# 16ServosController.net
KiCad netlist of a schematic drawn in EAGLE
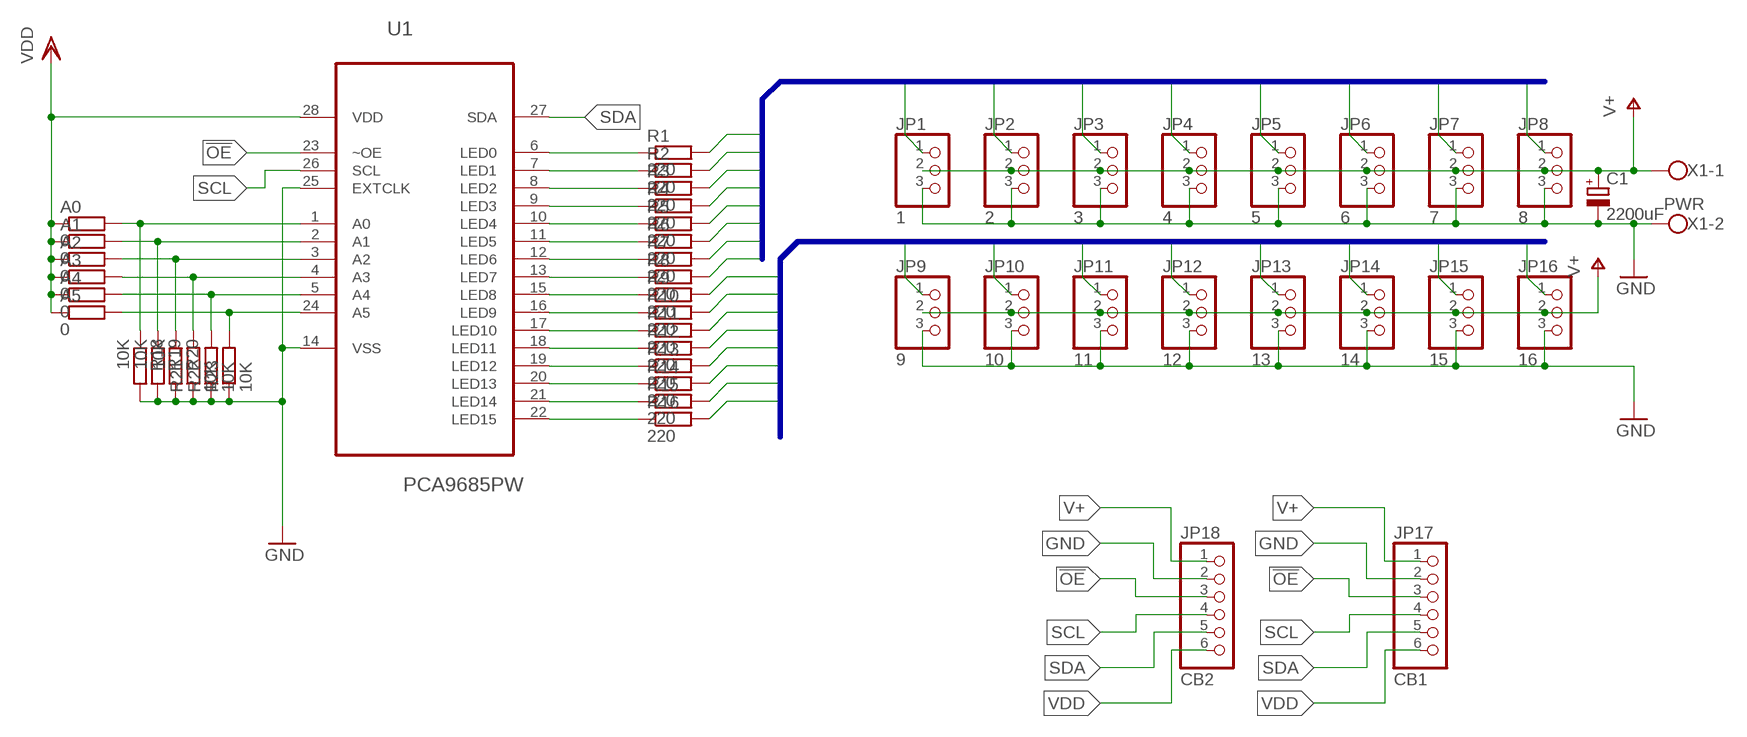
[diagram p0: schematic, sheet 1]

(export (version "E")
  (design (tool "Eeschema 10.0.6"))
  (components
    (comp (ref "A0")
      (value "0")
      (footprint "eagle-import:R0805")
      (libsource (lib "eagle-import") (part "R-EU_R0805"))
    )
    (comp (ref "A1")
      (value "0")
      (footprint "eagle-import:R0805")
      (libsource (lib "eagle-import") (part "R-EU_R0805"))
    )
    (comp (ref "A2")
      (value "0")
      (footprint "eagle-import:R0805")
      (libsource (lib "eagle-import") (part "R-EU_R0805"))
    )
    (comp (ref "A3")
      (value "0")
      (footprint "eagle-import:R0805")
      (libsource (lib "eagle-import") (part "R-EU_R0805"))
    )
    (comp (ref "A4")
      (value "0")
      (footprint "eagle-import:R0805")
      (libsource (lib "eagle-import") (part "R-EU_R0805"))
    )
    (comp (ref "A5")
      (value "0")
      (footprint "eagle-import:R0805")
      (libsource (lib "eagle-import") (part "R-EU_R0805"))
    )
    (comp (ref "C1")
      (value "2200uF")
      (footprint "eagle-import:E5-6")
      (libsource (lib "eagle-import") (part "CPOL-EUE5-6"))
    )
    (comp (ref "JP1")
      (value "1")
      (footprint "eagle-import:1X03")
      (libsource (lib "eagle-import") (part "PINHD-1X3"))
    )
    (comp (ref "JP2")
      (value "2")
      (footprint "eagle-import:1X03")
      (libsource (lib "eagle-import") (part "PINHD-1X3"))
    )
    (comp (ref "JP3")
      (value "3")
      (footprint "eagle-import:1X03")
      (libsource (lib "eagle-import") (part "PINHD-1X3"))
    )
    (comp (ref "JP4")
      (value "4")
      (footprint "eagle-import:1X03")
      (libsource (lib "eagle-import") (part "PINHD-1X3"))
    )
    (comp (ref "JP5")
      (value "5")
      (footprint "eagle-import:1X03")
      (libsource (lib "eagle-import") (part "PINHD-1X3"))
    )
    (comp (ref "JP6")
      (value "6")
      (footprint "eagle-import:1X03")
      (libsource (lib "eagle-import") (part "PINHD-1X3"))
    )
    (comp (ref "JP7")
      (value "7")
      (footprint "eagle-import:1X03")
      (libsource (lib "eagle-import") (part "PINHD-1X3"))
    )
    (comp (ref "JP8")
      (value "8")
      (footprint "eagle-import:1X03")
      (libsource (lib "eagle-import") (part "PINHD-1X3"))
    )
    (comp (ref "JP9")
      (value "9")
      (footprint "eagle-import:1X03")
      (libsource (lib "eagle-import") (part "PINHD-1X3"))
    )
    (comp (ref "JP10")
      (value "10")
      (footprint "eagle-import:1X03")
      (libsource (lib "eagle-import") (part "PINHD-1X3"))
    )
    (comp (ref "JP11")
      (value "11")
      (footprint "eagle-import:1X03")
      (libsource (lib "eagle-import") (part "PINHD-1X3"))
    )
    (comp (ref "JP12")
      (value "12")
      (footprint "eagle-import:1X03")
      (libsource (lib "eagle-import") (part "PINHD-1X3"))
    )
    (comp (ref "JP13")
      (value "13")
      (footprint "eagle-import:1X03")
      (libsource (lib "eagle-import") (part "PINHD-1X3"))
    )
    (comp (ref "JP14")
      (value "14")
      (footprint "eagle-import:1X03")
      (libsource (lib "eagle-import") (part "PINHD-1X3"))
    )
    (comp (ref "JP15")
      (value "15")
      (footprint "eagle-import:1X03")
      (libsource (lib "eagle-import") (part "PINHD-1X3"))
    )
    (comp (ref "JP16")
      (value "16")
      (footprint "eagle-import:1X03")
      (libsource (lib "eagle-import") (part "PINHD-1X3"))
    )
    (comp (ref "JP17")
      (value "CB1")
      (footprint "eagle-import:1X06")
      (libsource (lib "eagle-import") (part "PINHD-1X6"))
    )
    (comp (ref "JP18")
      (value "CB2")
      (footprint "eagle-import:1X06")
      (libsource (lib "eagle-import") (part "PINHD-1X6"))
    )
    (comp (ref "R1")
      (value "220")
      (footprint "eagle-import:R0805")
      (libsource (lib "eagle-import") (part "R-EU_R0805"))
    )
    (comp (ref "R2")
      (value "220")
      (footprint "eagle-import:R0805")
      (libsource (lib "eagle-import") (part "R-EU_R0805"))
    )
    (comp (ref "R3")
      (value "220")
      (footprint "eagle-import:R0805")
      (libsource (lib "eagle-import") (part "R-EU_R0805"))
    )
    (comp (ref "R4")
      (value "220")
      (footprint "eagle-import:R0805")
      (libsource (lib "eagle-import") (part "R-EU_R0805"))
    )
    (comp (ref "R5")
      (value "220")
      (footprint "eagle-import:R0805")
      (libsource (lib "eagle-import") (part "R-EU_R0805"))
    )
    (comp (ref "R6")
      (value "220")
      (footprint "eagle-import:R0805")
      (libsource (lib "eagle-import") (part "R-EU_R0805"))
    )
    (comp (ref "R7")
      (value "220")
      (footprint "eagle-import:R0805")
      (libsource (lib "eagle-import") (part "R-EU_R0805"))
    )
    (comp (ref "R8")
      (value "220")
      (footprint "eagle-import:R0805")
      (libsource (lib "eagle-import") (part "R-EU_R0805"))
    )
    (comp (ref "R9")
      (value "220")
      (footprint "eagle-import:R0805")
      (libsource (lib "eagle-import") (part "R-EU_R0805"))
    )
    (comp (ref "R10")
      (value "220")
      (footprint "eagle-import:R0805")
      (libsource (lib "eagle-import") (part "R-EU_R0805"))
    )
    (comp (ref "R11")
      (value "220")
      (footprint "eagle-import:R0805")
      (libsource (lib "eagle-import") (part "R-EU_R0805"))
    )
    (comp (ref "R12")
      (value "220")
      (footprint "eagle-import:R0805")
      (libsource (lib "eagle-import") (part "R-EU_R0805"))
    )
    (comp (ref "R13")
      (value "220")
      (footprint "eagle-import:R0805")
      (libsource (lib "eagle-import") (part "R-EU_R0805"))
    )
    (comp (ref "R14")
      (value "220")
      (footprint "eagle-import:R0805")
      (libsource (lib "eagle-import") (part "R-EU_R0805"))
    )
    (comp (ref "R15")
      (value "220")
      (footprint "eagle-import:R0805")
      (libsource (lib "eagle-import") (part "R-EU_R0805"))
    )
    (comp (ref "R16")
      (value "220")
      (footprint "eagle-import:R0805")
      (libsource (lib "eagle-import") (part "R-EU_R0805"))
    )
    (comp (ref "R18")
      (value "10K")
      (footprint "eagle-import:R0805")
      (libsource (lib "eagle-import") (part "R-EU_R0805"))
    )
    (comp (ref "R19")
      (value "10K")
      (footprint "eagle-import:R0805")
      (libsource (lib "eagle-import") (part "R-EU_R0805"))
    )
    (comp (ref "R20")
      (value "10K")
      (footprint "eagle-import:R0805")
      (libsource (lib "eagle-import") (part "R-EU_R0805"))
    )
    (comp (ref "R21")
      (value "10K")
      (footprint "eagle-import:R0805")
      (libsource (lib "eagle-import") (part "R-EU_R0805"))
    )
    (comp (ref "R22")
      (value "10K")
      (footprint "eagle-import:R0805")
      (libsource (lib "eagle-import") (part "R-EU_R0805"))
    )
    (comp (ref "R23")
      (value "10K")
      (footprint "eagle-import:R0805")
      (libsource (lib "eagle-import") (part "R-EU_R0805"))
    )
    (comp (ref "U1")
      (value "PCA9685PW")
      (footprint "eagle-import:SOP65P640X110-28N")
      (libsource (lib "eagle-import") (part "PCA9685PW"))
    )
    (comp (ref "X1")
      (value "PWR")
      (footprint "eagle-import:W237-102")
      (fields (field (name "MPN") "237-102"))
      (libsource (lib "eagle-import") (part "W237-102"))
    )
  )
  (nets
    (net (code "1") (name "/PWM1") (class "Default")
      (node (ref "JP1") (pin "1") (pinfunction "1_1") (pintype "passive"))
      (node (ref "R1") (pin "2") (pinfunction "2_2") (pintype "passive"))
    )
    (net (code "2") (name "/PWM2") (class "Default")
      (node (ref "JP2") (pin "1") (pinfunction "1_1") (pintype "passive"))
      (node (ref "R2") (pin "2") (pinfunction "2_2") (pintype "passive"))
    )
    (net (code "3") (name "/PWM3") (class "Default")
      (node (ref "JP3") (pin "1") (pinfunction "1_1") (pintype "passive"))
      (node (ref "R3") (pin "2") (pinfunction "2_2") (pintype "passive"))
    )
    (net (code "4") (name "/PWM4") (class "Default")
      (node (ref "JP4") (pin "1") (pinfunction "1_1") (pintype "passive"))
      (node (ref "R4") (pin "2") (pinfunction "2_2") (pintype "passive"))
    )
    (net (code "5") (name "/PWM5") (class "Default")
      (node (ref "JP5") (pin "1") (pinfunction "1_1") (pintype "passive"))
      (node (ref "R5") (pin "2") (pinfunction "2_2") (pintype "passive"))
    )
    (net (code "6") (name "/PWM6") (class "Default")
      (node (ref "JP6") (pin "1") (pinfunction "1_1") (pintype "passive"))
      (node (ref "R6") (pin "2") (pinfunction "2_2") (pintype "passive"))
    )
    (net (code "7") (name "/PWM7") (class "Default")
      (node (ref "JP7") (pin "1") (pinfunction "1_1") (pintype "passive"))
      (node (ref "R7") (pin "2") (pinfunction "2_2") (pintype "passive"))
    )
    (net (code "8") (name "/PWM8") (class "Default")
      (node (ref "JP8") (pin "1") (pinfunction "1_1") (pintype "passive"))
      (node (ref "R8") (pin "2") (pinfunction "2_2") (pintype "passive"))
    )
    (net (code "9") (name "/PWM9") (class "Default")
      (node (ref "JP9") (pin "1") (pinfunction "1_1") (pintype "passive"))
      (node (ref "R9") (pin "2") (pinfunction "2_2") (pintype "passive"))
    )
    (net (code "10") (name "/PWM10") (class "Default")
      (node (ref "JP10") (pin "1") (pinfunction "1_1") (pintype "passive"))
      (node (ref "R10") (pin "2") (pinfunction "2_2") (pintype "passive"))
    )
    (net (code "11") (name "/PWM11") (class "Default")
      (node (ref "JP11") (pin "1") (pinfunction "1_1") (pintype "passive"))
      (node (ref "R11") (pin "2") (pinfunction "2_2") (pintype "passive"))
    )
    (net (code "12") (name "/PWM12") (class "Default")
      (node (ref "JP12") (pin "1") (pinfunction "1_1") (pintype "passive"))
      (node (ref "R12") (pin "2") (pinfunction "2_2") (pintype "passive"))
    )
    (net (code "13") (name "/PWM13") (class "Default")
      (node (ref "JP13") (pin "1") (pinfunction "1_1") (pintype "passive"))
      (node (ref "R13") (pin "2") (pinfunction "2_2") (pintype "passive"))
    )
    (net (code "14") (name "/PWM14") (class "Default")
      (node (ref "JP14") (pin "1") (pinfunction "1_1") (pintype "passive"))
      (node (ref "R14") (pin "2") (pinfunction "2_2") (pintype "passive"))
    )
    (net (code "15") (name "/PWM15") (class "Default")
      (node (ref "JP15") (pin "1") (pinfunction "1_1") (pintype "passive"))
      (node (ref "R15") (pin "2") (pinfunction "2_2") (pintype "passive"))
    )
    (net (code "16") (name "/PWM16") (class "Default")
      (node (ref "JP16") (pin "1") (pinfunction "1_1") (pintype "passive"))
      (node (ref "R16") (pin "2") (pinfunction "2_2") (pintype "passive"))
    )
    (net (code "17") (name "/~{OE}") (class "Default")
      (node (ref "JP17") (pin "3") (pinfunction "3_3") (pintype "passive"))
      (node (ref "JP18") (pin "3") (pinfunction "3_3") (pintype "passive"))
      (node (ref "U1") (pin "23") (pinfunction "~{OE}_23") (pintype "input"))
    )
    (net (code "18") (name "GND") (class "Default")
      (node (ref "C1") (pin "-") (pinfunction "-_-") (pintype "passive"))
      (node (ref "JP1") (pin "3") (pinfunction "3_3") (pintype "passive"))
      (node (ref "JP10") (pin "3") (pinfunction "3_3") (pintype "passive"))
      (node (ref "JP11") (pin "3") (pinfunction "3_3") (pintype "passive"))
      (node (ref "JP12") (pin "3") (pinfunction "3_3") (pintype "passive"))
      (node (ref "JP13") (pin "3") (pinfunction "3_3") (pintype "passive"))
      (node (ref "JP14") (pin "3") (pinfunction "3_3") (pintype "passive"))
      (node (ref "JP15") (pin "3") (pinfunction "3_3") (pintype "passive"))
      (node (ref "JP16") (pin "3") (pinfunction "3_3") (pintype "passive"))
      (node (ref "JP17") (pin "2") (pinfunction "2_2") (pintype "passive"))
      (node (ref "JP18") (pin "2") (pinfunction "2_2") (pintype "passive"))
      (node (ref "JP2") (pin "3") (pinfunction "3_3") (pintype "passive"))
      (node (ref "JP3") (pin "3") (pinfunction "3_3") (pintype "passive"))
      (node (ref "JP4") (pin "3") (pinfunction "3_3") (pintype "passive"))
      (node (ref "JP5") (pin "3") (pinfunction "3_3") (pintype "passive"))
      (node (ref "JP6") (pin "3") (pinfunction "3_3") (pintype "passive"))
      (node (ref "JP7") (pin "3") (pinfunction "3_3") (pintype "passive"))
      (node (ref "JP8") (pin "3") (pinfunction "3_3") (pintype "passive"))
      (node (ref "JP9") (pin "3") (pinfunction "3_3") (pintype "passive"))
      (node (ref "R18") (pin "2") (pinfunction "2_2") (pintype "passive"))
      (node (ref "R19") (pin "2") (pinfunction "2_2") (pintype "passive"))
      (node (ref "R20") (pin "2") (pinfunction "2_2") (pintype "passive"))
      (node (ref "R21") (pin "1") (pinfunction "1_1") (pintype "passive"))
      (node (ref "R22") (pin "1") (pinfunction "1_1") (pintype "passive"))
      (node (ref "R23") (pin "1") (pinfunction "1_1") (pintype "passive"))
      (node (ref "U1") (pin "14") (pinfunction "VSS_14") (pintype "passive"))
      (node (ref "U1") (pin "25") (pinfunction "EXTCLK_25") (pintype "input"))
      (node (ref "X1") (pin "2") (pinfunction "KL_2") (pintype "passive"))
    )
    (net (code "19") (name "Net-(U1-A0)") (class "Default")
      (node (ref "A0") (pin "2") (pinfunction "2_2") (pintype "passive"))
      (node (ref "R18") (pin "1") (pinfunction "1_1") (pintype "passive"))
      (node (ref "U1") (pin "1") (pinfunction "A0_1") (pintype "input"))
    )
    (net (code "20") (name "Net-(U1-A1)") (class "Default")
      (node (ref "A1") (pin "2") (pinfunction "2_2") (pintype "passive"))
      (node (ref "R19") (pin "1") (pinfunction "1_1") (pintype "passive"))
      (node (ref "U1") (pin "2") (pinfunction "A1_2") (pintype "input"))
    )
    (net (code "21") (name "Net-(U1-A2)") (class "Default")
      (node (ref "A2") (pin "2") (pinfunction "2_2") (pintype "passive"))
      (node (ref "R20") (pin "1") (pinfunction "1_1") (pintype "passive"))
      (node (ref "U1") (pin "3") (pinfunction "A2_3") (pintype "input"))
    )
    (net (code "22") (name "Net-(U1-A3)") (class "Default")
      (node (ref "A3") (pin "2") (pinfunction "2_2") (pintype "passive"))
      (node (ref "R21") (pin "2") (pinfunction "2_2") (pintype "passive"))
      (node (ref "U1") (pin "4") (pinfunction "A3_4") (pintype "input"))
    )
    (net (code "23") (name "Net-(U1-A4)") (class "Default")
      (node (ref "A4") (pin "2") (pinfunction "2_2") (pintype "passive"))
      (node (ref "R22") (pin "2") (pinfunction "2_2") (pintype "passive"))
      (node (ref "U1") (pin "5") (pinfunction "A4_5") (pintype "input"))
    )
    (net (code "24") (name "Net-(U1-A5)") (class "Default")
      (node (ref "A5") (pin "2") (pinfunction "2_2") (pintype "passive"))
      (node (ref "R23") (pin "2") (pinfunction "2_2") (pintype "passive"))
      (node (ref "U1") (pin "24") (pinfunction "A5_24") (pintype "input"))
    )
    (net (code "25") (name "Net-(U1-LED0)") (class "Default")
      (node (ref "R1") (pin "1") (pinfunction "1_1") (pintype "passive"))
      (node (ref "U1") (pin "6") (pinfunction "LED0_6") (pintype "output"))
    )
    (net (code "26") (name "Net-(U1-LED1)") (class "Default")
      (node (ref "R2") (pin "1") (pinfunction "1_1") (pintype "passive"))
      (node (ref "U1") (pin "7") (pinfunction "LED1_7") (pintype "output"))
    )
    (net (code "27") (name "Net-(U1-LED2)") (class "Default")
      (node (ref "R3") (pin "1") (pinfunction "1_1") (pintype "passive"))
      (node (ref "U1") (pin "8") (pinfunction "LED2_8") (pintype "output"))
    )
    (net (code "28") (name "Net-(U1-LED3)") (class "Default")
      (node (ref "R4") (pin "1") (pinfunction "1_1") (pintype "passive"))
      (node (ref "U1") (pin "9") (pinfunction "LED3_9") (pintype "output"))
    )
    (net (code "29") (name "Net-(U1-LED4)") (class "Default")
      (node (ref "R5") (pin "1") (pinfunction "1_1") (pintype "passive"))
      (node (ref "U1") (pin "10") (pinfunction "LED4_10") (pintype "output"))
    )
    (net (code "30") (name "Net-(U1-LED5)") (class "Default")
      (node (ref "R6") (pin "1") (pinfunction "1_1") (pintype "passive"))
      (node (ref "U1") (pin "11") (pinfunction "LED5_11") (pintype "output"))
    )
    (net (code "31") (name "Net-(U1-LED6)") (class "Default")
      (node (ref "R7") (pin "1") (pinfunction "1_1") (pintype "passive"))
      (node (ref "U1") (pin "12") (pinfunction "LED6_12") (pintype "output"))
    )
    (net (code "32") (name "Net-(U1-LED7)") (class "Default")
      (node (ref "R8") (pin "1") (pinfunction "1_1") (pintype "passive"))
      (node (ref "U1") (pin "13") (pinfunction "LED7_13") (pintype "output"))
    )
    (net (code "33") (name "Net-(U1-LED8)") (class "Default")
      (node (ref "R9") (pin "1") (pinfunction "1_1") (pintype "passive"))
      (node (ref "U1") (pin "15") (pinfunction "LED8_15") (pintype "output"))
    )
    (net (code "34") (name "Net-(U1-LED9)") (class "Default")
      (node (ref "R10") (pin "1") (pinfunction "1_1") (pintype "passive"))
      (node (ref "U1") (pin "16") (pinfunction "LED9_16") (pintype "output"))
    )
    (net (code "35") (name "Net-(U1-LED10)") (class "Default")
      (node (ref "R11") (pin "1") (pinfunction "1_1") (pintype "passive"))
      (node (ref "U1") (pin "17") (pinfunction "LED10_17") (pintype "output"))
    )
    (net (code "36") (name "Net-(U1-LED11)") (class "Default")
      (node (ref "R12") (pin "1") (pinfunction "1_1") (pintype "passive"))
      (node (ref "U1") (pin "18") (pinfunction "LED11_18") (pintype "output"))
    )
    (net (code "37") (name "Net-(U1-LED12)") (class "Default")
      (node (ref "R13") (pin "1") (pinfunction "1_1") (pintype "passive"))
      (node (ref "U1") (pin "19") (pinfunction "LED12_19") (pintype "output"))
    )
    (net (code "38") (name "Net-(U1-LED13)") (class "Default")
      (node (ref "R14") (pin "1") (pinfunction "1_1") (pintype "passive"))
      (node (ref "U1") (pin "20") (pinfunction "LED13_20") (pintype "output"))
    )
    (net (code "39") (name "Net-(U1-LED14)") (class "Default")
      (node (ref "R15") (pin "1") (pinfunction "1_1") (pintype "passive"))
      (node (ref "U1") (pin "21") (pinfunction "LED14_21") (pintype "output"))
    )
    (net (code "40") (name "Net-(U1-LED15)") (class "Default")
      (node (ref "R16") (pin "1") (pinfunction "1_1") (pintype "passive"))
      (node (ref "U1") (pin "22") (pinfunction "LED15_22") (pintype "output"))
    )
    (net (code "41") (name "SCL") (class "Default")
      (node (ref "JP17") (pin "4") (pinfunction "4_4") (pintype "passive"))
      (node (ref "JP18") (pin "4") (pinfunction "4_4") (pintype "passive"))
      (node (ref "U1") (pin "26") (pinfunction "SCL_26") (pintype "input"))
    )
    (net (code "42") (name "SDA") (class "Default")
      (node (ref "JP17") (pin "5") (pinfunction "5_5") (pintype "passive"))
      (node (ref "JP18") (pin "5") (pinfunction "5_5") (pintype "passive"))
      (node (ref "U1") (pin "27") (pinfunction "SDA_27") (pintype "bidirectional"))
    )
    (net (code "43") (name "V+") (class "Default")
      (node (ref "C1") (pin "+") (pinfunction "+_+") (pintype "passive"))
      (node (ref "JP1") (pin "2") (pinfunction "2_2") (pintype "passive"))
      (node (ref "JP10") (pin "2") (pinfunction "2_2") (pintype "passive"))
      (node (ref "JP11") (pin "2") (pinfunction "2_2") (pintype "passive"))
      (node (ref "JP12") (pin "2") (pinfunction "2_2") (pintype "passive"))
      (node (ref "JP13") (pin "2") (pinfunction "2_2") (pintype "passive"))
      (node (ref "JP14") (pin "2") (pinfunction "2_2") (pintype "passive"))
      (node (ref "JP15") (pin "2") (pinfunction "2_2") (pintype "passive"))
      (node (ref "JP16") (pin "2") (pinfunction "2_2") (pintype "passive"))
      (node (ref "JP17") (pin "1") (pinfunction "1_1") (pintype "passive"))
      (node (ref "JP18") (pin "1") (pinfunction "1_1") (pintype "passive"))
      (node (ref "JP2") (pin "2") (pinfunction "2_2") (pintype "passive"))
      (node (ref "JP3") (pin "2") (pinfunction "2_2") (pintype "passive"))
      (node (ref "JP4") (pin "2") (pinfunction "2_2") (pintype "passive"))
      (node (ref "JP5") (pin "2") (pinfunction "2_2") (pintype "passive"))
      (node (ref "JP6") (pin "2") (pinfunction "2_2") (pintype "passive"))
      (node (ref "JP7") (pin "2") (pinfunction "2_2") (pintype "passive"))
      (node (ref "JP8") (pin "2") (pinfunction "2_2") (pintype "passive"))
      (node (ref "JP9") (pin "2") (pinfunction "2_2") (pintype "passive"))
      (node (ref "X1") (pin "1") (pinfunction "KL_1") (pintype "passive"))
    )
    (net (code "44") (name "VDD") (class "Default")
      (node (ref "A0") (pin "1") (pinfunction "1_1") (pintype "passive"))
      (node (ref "A1") (pin "1") (pinfunction "1_1") (pintype "passive"))
      (node (ref "A2") (pin "1") (pinfunction "1_1") (pintype "passive"))
      (node (ref "A3") (pin "1") (pinfunction "1_1") (pintype "passive"))
      (node (ref "A4") (pin "1") (pinfunction "1_1") (pintype "passive"))
      (node (ref "A5") (pin "1") (pinfunction "1_1") (pintype "passive"))
      (node (ref "JP17") (pin "6") (pinfunction "6_6") (pintype "passive"))
      (node (ref "JP18") (pin "6") (pinfunction "6_6") (pintype "passive"))
      (node (ref "U1") (pin "28") (pinfunction "VDD_28") (pintype "power_in"))
    )
  )
)
